# pcb-bme280-breakout.net
KiCad netlist of a schematic drawn in EAGLE
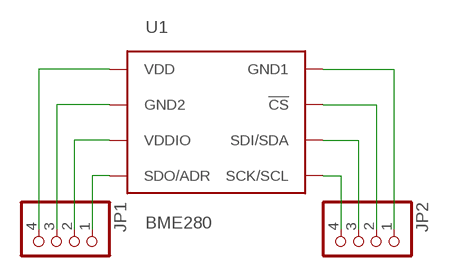
[diagram p0: schematic, sheet 1]

(export (version "E")
  (design (tool "Eeschema 10.0.6"))
  (components
    (comp (ref "JP1")
      (value "PINHD-1X4")
      (footprint "eagle-import:1X04")
      (libsource (lib "eagle-import") (part "PINHD-1X4"))
    )
    (comp (ref "JP2")
      (value "PINHD-1X4")
      (footprint "eagle-import:1X04")
      (libsource (lib "eagle-import") (part "PINHD-1X4"))
    )
    (comp (ref "U1")
      (value "BME280")
      (footprint "eagle-import:BME280_LGA")
      (libsource (lib "eagle-import") (part "BME280"))
    )
  )
  (nets
    (net (code "1") (name "Net-(U1-GND1)") (class "Default")
      (node (ref "JP2") (pin "1") (pinfunction "1_1") (pintype "passive"))
      (node (ref "U1") (pin "P$1") (pinfunction "GND1_P$1") (pintype "bidirectional"))
    )
    (net (code "2") (name "Net-(U1-GND2)") (class "Default")
      (node (ref "JP1") (pin "3") (pinfunction "3_3") (pintype "passive"))
      (node (ref "U1") (pin "P$7") (pinfunction "GND2_P$7") (pintype "bidirectional"))
    )
    (net (code "3") (name "Net-(U1-SCK{slash}SCL)") (class "Default")
      (node (ref "JP2") (pin "4") (pinfunction "4_4") (pintype "passive"))
      (node (ref "U1") (pin "P$4") (pinfunction "SCK/SCL_P$4") (pintype "bidirectional"))
    )
    (net (code "4") (name "Net-(U1-SDI{slash}SDA)") (class "Default")
      (node (ref "JP2") (pin "3") (pinfunction "3_3") (pintype "passive"))
      (node (ref "U1") (pin "P$3") (pinfunction "SDI/SDA_P$3") (pintype "bidirectional"))
    )
    (net (code "5") (name "Net-(U1-SDO{slash}ADR)") (class "Default")
      (node (ref "JP1") (pin "1") (pinfunction "1_1") (pintype "passive"))
      (node (ref "U1") (pin "P$5") (pinfunction "SDO/ADR_P$5") (pintype "bidirectional"))
    )
    (net (code "6") (name "Net-(U1-VDD)") (class "Default")
      (node (ref "JP1") (pin "4") (pinfunction "4_4") (pintype "passive"))
      (node (ref "U1") (pin "P$8") (pinfunction "VDD_P$8") (pintype "bidirectional"))
    )
    (net (code "7") (name "Net-(U1-VDDIO)") (class "Default")
      (node (ref "JP1") (pin "2") (pinfunction "2_2") (pintype "passive"))
      (node (ref "U1") (pin "P$6") (pinfunction "VDDIO_P$6") (pintype "bidirectional"))
    )
    (net (code "8") (name "Net-(U1-~{CS})") (class "Default")
      (node (ref "JP2") (pin "2") (pinfunction "2_2") (pintype "passive"))
      (node (ref "U1") (pin "P$2") (pinfunction "~{CS}_P$2") (pintype "bidirectional"))
    )
  )
)
